# prozeda_0_2.net
KiCad netlist of a schematic drawn in EAGLE
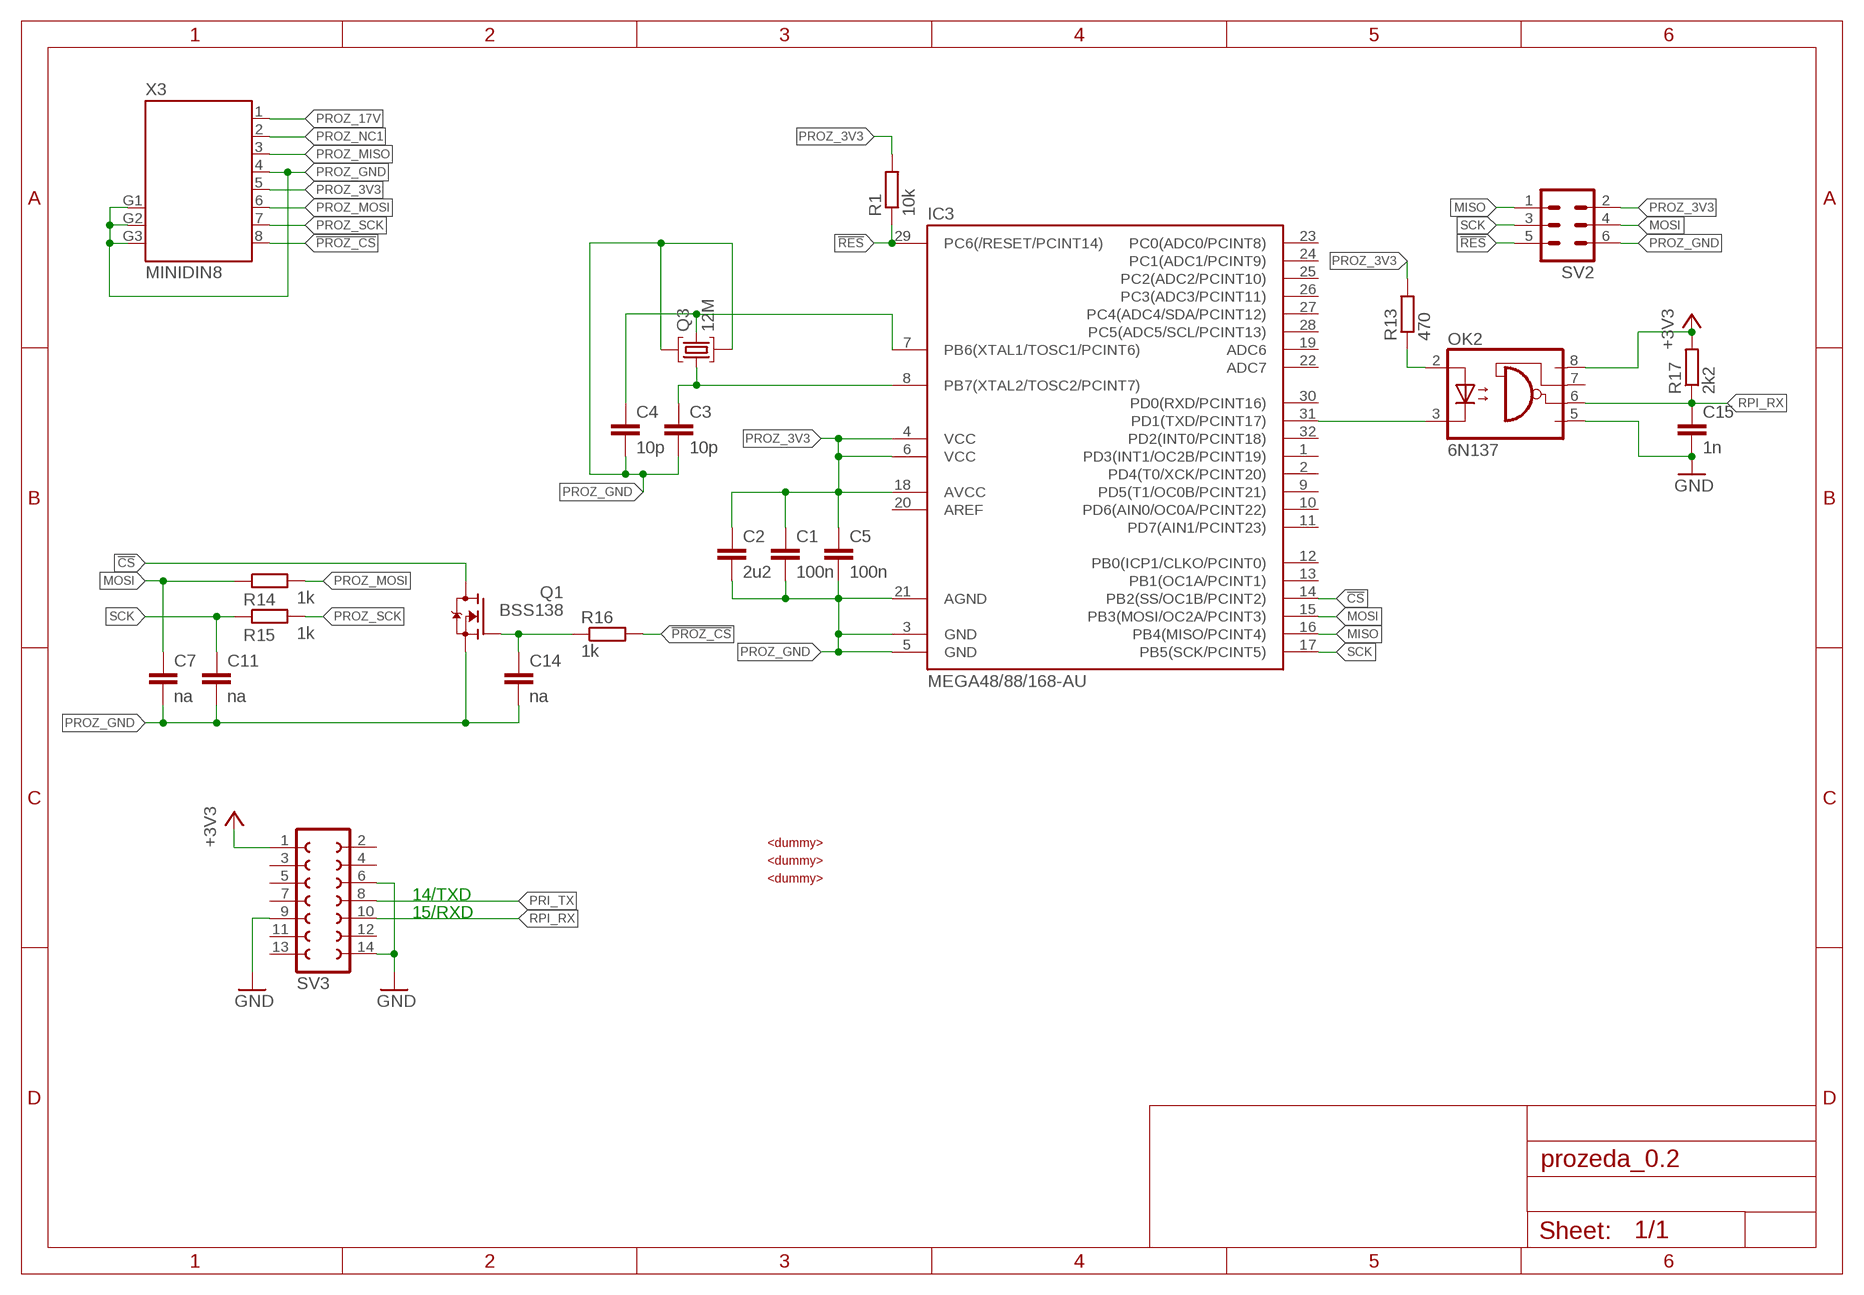
[diagram p0: schematic, sheet 1]

(export (version "E")
  (design (tool "Eeschema 10.0.6"))
  (components
    (comp (ref "C1")
      (value "100n")
      (footprint "eagle-import:C0603")
      (libsource (lib "eagle-import") (part "C-EUC0603"))
    )
    (comp (ref "C2")
      (value "2u2")
      (footprint "eagle-import:C0805")
      (libsource (lib "eagle-import") (part "C-EUC0805"))
    )
    (comp (ref "C3")
      (value "10p")
      (footprint "eagle-import:C0603")
      (libsource (lib "eagle-import") (part "C-EUC0603"))
    )
    (comp (ref "C4")
      (value "10p")
      (footprint "eagle-import:C0603")
      (libsource (lib "eagle-import") (part "C-EUC0603"))
    )
    (comp (ref "C5")
      (value "100n")
      (footprint "eagle-import:C0603")
      (libsource (lib "eagle-import") (part "C-EUC0603"))
    )
    (comp (ref "C7")
      (value "na")
      (footprint "eagle-import:C0603")
      (libsource (lib "eagle-import") (part "C-EUC0603"))
    )
    (comp (ref "C11")
      (value "na")
      (footprint "eagle-import:C0603")
      (libsource (lib "eagle-import") (part "C-EUC0603"))
    )
    (comp (ref "C14")
      (value "na")
      (footprint "eagle-import:C0603")
      (libsource (lib "eagle-import") (part "C-EUC0603"))
    )
    (comp (ref "C15")
      (value "1n")
      (footprint "eagle-import:C0603")
      (libsource (lib "eagle-import") (part "C-EUC0603"))
    )
    (comp (ref "IC3")
      (value "MEGA48/88/168-AU")
      (footprint "eagle-import:TQFP32-08")
      (libsource (lib "eagle-import") (part "MEGA48/88/168-AU"))
    )
    (comp (ref "OK2")
      (value "6N137")
      (footprint "eagle-import:DIL08")
      (libsource (lib "eagle-import") (part "6N137"))
    )
    (comp (ref "Q1")
      (value "BSS138")
      (footprint "eagle-import:SOT23")
      (libsource (lib "eagle-import") (part "BSS138"))
    )
    (comp (ref "Q3")
      (value "12M")
      (footprint "eagle-import:MJ")
      (libsource (lib "eagle-import") (part "SMD4PADMJ"))
    )
    (comp (ref "R1")
      (value "10k")
      (footprint "eagle-import:R0603")
      (libsource (lib "eagle-import") (part "R-EU_R0603"))
    )
    (comp (ref "R13")
      (value "470")
      (footprint "eagle-import:R0603")
      (libsource (lib "eagle-import") (part "R-EU_R0603"))
    )
    (comp (ref "R14")
      (value "1k")
      (footprint "eagle-import:R0603")
      (libsource (lib "eagle-import") (part "R-EU_R0603"))
    )
    (comp (ref "R15")
      (value "1k")
      (footprint "eagle-import:R0603")
      (libsource (lib "eagle-import") (part "R-EU_R0603"))
    )
    (comp (ref "R16")
      (value "1k")
      (footprint "eagle-import:R0603")
      (libsource (lib "eagle-import") (part "R-EU_R0603"))
    )
    (comp (ref "R17")
      (value "2k2")
      (footprint "eagle-import:R0603")
      (libsource (lib "eagle-import") (part "R-EU_R0603"))
    )
    (comp (ref "SV2")
      (value "MA03-2")
      (footprint "eagle-import:MA03-2")
      (libsource (lib "eagle-import") (part "MA03-2"))
    )
    (comp (ref "SV3")
      (value "FE07-2")
      (footprint "eagle-import:FE07-2")
      (libsource (lib "eagle-import") (part "FE07-2"))
    )
    (comp (ref "U$1")
      (value "DUMMY")
      (footprint "eagle-import:DUMMY")
      (libsource (lib "eagle-import") (part "DUMMY"))
    )
    (comp (ref "U$2")
      (value "DUMMY")
      (footprint "eagle-import:DUMMY")
      (libsource (lib "eagle-import") (part "DUMMY"))
    )
    (comp (ref "U$3")
      (value "DUMMY")
      (footprint "eagle-import:DUMMY")
      (libsource (lib "eagle-import") (part "DUMMY"))
    )
    (comp (ref "X3")
      (value "MINIDIN8")
      (footprint "eagle-import:MINI-DIN8")
      (libsource (lib "eagle-import") (part "MINIDIN8"))
    )
  )
  (nets
    (net (code "1") (name "+3V3") (class "Default")
      (node (ref "OK2") (pin "8") (pinfunction "VCC_8") (pintype "passive"))
      (node (ref "R17") (pin "2") (pinfunction "2_2") (pintype "passive"))
      (node (ref "SV3") (pin "1") (pinfunction "1_1") (pintype "passive"))
    )
    (net (code "2") (name "/~{CS}") (class "Default")
      (node (ref "IC3") (pin "14") (pinfunction "PB2(SS/OC1B/PCINT2)_14") (pintype "bidirectional"))
      (node (ref "Q1") (pin "3") (pinfunction "D_3") (pintype "passive"))
    )
    (net (code "3") (name "/~{PROZ_CS}") (class "Default")
      (node (ref "R16") (pin "2") (pinfunction "2_2") (pintype "passive"))
      (node (ref "X3") (pin "8") (pinfunction "P$8_8") (pintype "bidirectional"))
    )
    (net (code "4") (name "/~{RES}") (class "Default")
      (node (ref "IC3") (pin "29") (pinfunction "PC6(/RESET/PCINT14)_29") (pintype "bidirectional"))
      (node (ref "R1") (pin "1") (pinfunction "1_1") (pintype "passive"))
      (node (ref "SV2") (pin "5") (pinfunction "5_5") (pintype "passive"))
    )
    (net (code "5") (name "GND") (class "Default")
      (node (ref "C15") (pin "2") (pinfunction "2_2") (pintype "passive"))
      (node (ref "OK2") (pin "5") (pinfunction "GND_5") (pintype "passive"))
      (node (ref "SV3") (pin "14") (pinfunction "14_14") (pintype "passive"))
      (node (ref "SV3") (pin "6") (pinfunction "6_6") (pintype "passive"))
      (node (ref "SV3") (pin "9") (pinfunction "9_9") (pintype "passive"))
    )
    (net (code "6") (name "MISO") (class "Default")
      (node (ref "IC3") (pin "16") (pinfunction "PB4(MISO/PCINT4)_16") (pintype "bidirectional"))
      (node (ref "SV2") (pin "1") (pinfunction "1_1") (pintype "passive"))
    )
    (net (code "7") (name "MOSI") (class "Default")
      (node (ref "C7") (pin "1") (pinfunction "1_1") (pintype "passive"))
      (node (ref "IC3") (pin "15") (pinfunction "PB3(MOSI/OC2A/PCINT3)_15") (pintype "bidirectional"))
      (node (ref "R14") (pin "1") (pinfunction "1_1") (pintype "passive"))
      (node (ref "SV2") (pin "4") (pinfunction "4_4") (pintype "passive"))
    )
    (net (code "8") (name "Net-(IC3-PB6(XTAL1{slash}TOSC1{slash}PCINT6))") (class "Default")
      (node (ref "C4") (pin "1") (pinfunction "1_1") (pintype "passive"))
      (node (ref "IC3") (pin "7") (pinfunction "PB6(XTAL1/TOSC1/PCINT6)_7") (pintype "bidirectional"))
      (node (ref "Q3") (pin "3") (pinfunction "3_3") (pintype "passive"))
    )
    (net (code "9") (name "Net-(IC3-PB7(XTAL2{slash}TOSC2{slash}PCINT7))") (class "Default")
      (node (ref "C3") (pin "1") (pinfunction "1_1") (pintype "passive"))
      (node (ref "IC3") (pin "8") (pinfunction "PB7(XTAL2/TOSC2/PCINT7)_8") (pintype "bidirectional"))
      (node (ref "Q3") (pin "1") (pinfunction "1_1") (pintype "passive"))
    )
    (net (code "10") (name "Net-(IC3-PD1(TXD{slash}PCINT17))") (class "Default")
      (node (ref "IC3") (pin "31") (pinfunction "PD1(TXD/PCINT17)_31") (pintype "bidirectional"))
      (node (ref "OK2") (pin "3") (pinfunction "C_3") (pintype "passive"))
    )
    (net (code "11") (name "Net-(OK2-A)") (class "Default")
      (node (ref "OK2") (pin "2") (pinfunction "A_2") (pintype "passive"))
      (node (ref "R13") (pin "1") (pinfunction "1_1") (pintype "passive"))
    )
    (net (code "12") (name "Net-(Q1-G)") (class "Default")
      (node (ref "C14") (pin "1") (pinfunction "1_1") (pintype "passive"))
      (node (ref "Q1") (pin "1") (pinfunction "G_1") (pintype "passive"))
      (node (ref "R16") (pin "1") (pinfunction "1_1") (pintype "passive"))
    )
    (net (code "13") (name "PRI_TX") (class "Default")
      (node (ref "SV3") (pin "8") (pinfunction "8_8") (pintype "passive"))
    )
    (net (code "14") (name "PROZ_3V3") (class "Default")
      (node (ref "C1") (pin "1") (pinfunction "1_1") (pintype "passive"))
      (node (ref "C2") (pin "1") (pinfunction "1_1") (pintype "passive"))
      (node (ref "C5") (pin "1") (pinfunction "1_1") (pintype "passive"))
      (node (ref "IC3") (pin "18") (pinfunction "AVCC_18") (pintype "passive"))
      (node (ref "IC3") (pin "4") (pinfunction "VCC_4") (pintype "power_in"))
      (node (ref "IC3") (pin "6") (pinfunction "VCC_6") (pintype "power_in"))
      (node (ref "R1") (pin "2") (pinfunction "2_2") (pintype "passive"))
      (node (ref "R13") (pin "2") (pinfunction "2_2") (pintype "passive"))
      (node (ref "SV2") (pin "2") (pinfunction "2_2") (pintype "passive"))
      (node (ref "X3") (pin "5") (pinfunction "P$5_5") (pintype "bidirectional"))
    )
    (net (code "15") (name "PROZ_17V") (class "Default")
      (node (ref "X3") (pin "1") (pinfunction "P$1_1") (pintype "bidirectional"))
    )
    (net (code "16") (name "PROZ_GND") (class "Default")
      (node (ref "C1") (pin "2") (pinfunction "2_2") (pintype "passive"))
      (node (ref "C11") (pin "2") (pinfunction "2_2") (pintype "passive"))
      (node (ref "C14") (pin "2") (pinfunction "2_2") (pintype "passive"))
      (node (ref "C2") (pin "2") (pinfunction "2_2") (pintype "passive"))
      (node (ref "C3") (pin "2") (pinfunction "2_2") (pintype "passive"))
      (node (ref "C4") (pin "2") (pinfunction "2_2") (pintype "passive"))
      (node (ref "C5") (pin "2") (pinfunction "2_2") (pintype "passive"))
      (node (ref "C7") (pin "2") (pinfunction "2_2") (pintype "passive"))
      (node (ref "IC3") (pin "21") (pinfunction "AGND_21") (pintype "power_in"))
      (node (ref "IC3") (pin "3") (pinfunction "GND_3") (pintype "power_in"))
      (node (ref "IC3") (pin "5") (pinfunction "GND_5") (pintype "power_in"))
      (node (ref "Q1") (pin "2") (pinfunction "S_2") (pintype "passive"))
      (node (ref "Q3") (pin "2") (pinfunction "2_2") (pintype "passive"))
      (node (ref "Q3") (pin "4") (pinfunction "4_4") (pintype "passive"))
      (node (ref "SV2") (pin "6") (pinfunction "6_6") (pintype "passive"))
      (node (ref "X3") (pin "4") (pinfunction "P$4_4") (pintype "bidirectional"))
      (node (ref "X3") (pin "G1") (pinfunction "P$9_G1") (pintype "bidirectional"))
      (node (ref "X3") (pin "G2") (pinfunction "P$10_G2") (pintype "bidirectional"))
      (node (ref "X3") (pin "G3") (pinfunction "P$11_G3") (pintype "bidirectional"))
    )
    (net (code "17") (name "PROZ_MISO") (class "Default")
      (node (ref "X3") (pin "3") (pinfunction "P$3_3") (pintype "bidirectional"))
    )
    (net (code "18") (name "PROZ_MOSI") (class "Default")
      (node (ref "R14") (pin "2") (pinfunction "2_2") (pintype "passive"))
      (node (ref "X3") (pin "6") (pinfunction "P$6_6") (pintype "bidirectional"))
    )
    (net (code "19") (name "PROZ_NC1") (class "Default")
      (node (ref "X3") (pin "2") (pinfunction "P$2_2") (pintype "bidirectional"))
    )
    (net (code "20") (name "PROZ_SCK") (class "Default")
      (node (ref "R15") (pin "2") (pinfunction "2_2") (pintype "passive"))
      (node (ref "X3") (pin "7") (pinfunction "P$7_7") (pintype "bidirectional"))
    )
    (net (code "21") (name "RPI_RX") (class "Default")
      (node (ref "C15") (pin "1") (pinfunction "1_1") (pintype "passive"))
      (node (ref "OK2") (pin "6") (pinfunction "VO_6") (pintype "passive"))
      (node (ref "R17") (pin "1") (pinfunction "1_1") (pintype "passive"))
      (node (ref "SV3") (pin "10") (pinfunction "10_10") (pintype "passive"))
    )
    (net (code "22") (name "SCK") (class "Default")
      (node (ref "C11") (pin "1") (pinfunction "1_1") (pintype "passive"))
      (node (ref "IC3") (pin "17") (pinfunction "PB5(SCK/PCINT5)_17") (pintype "bidirectional"))
      (node (ref "R15") (pin "1") (pinfunction "1_1") (pintype "passive"))
      (node (ref "SV2") (pin "3") (pinfunction "3_3") (pintype "passive"))
    )
    (net (code "23") (name "unconnected-(IC3-ADC6-Pad19)") (class "Default")
      (node (ref "IC3") (pin "19") (pinfunction "ADC6_19") (pintype "passive"))
    )
    (net (code "24") (name "unconnected-(IC3-ADC7-Pad22)") (class "Default")
      (node (ref "IC3") (pin "22") (pinfunction "ADC7_22") (pintype "passive"))
    )
    (net (code "25") (name "unconnected-(IC3-AREF-Pad20)") (class "Default")
      (node (ref "IC3") (pin "20") (pinfunction "AREF_20") (pintype "passive"))
    )
    (net (code "26") (name "unconnected-(IC3-PB0(ICP1{slash}CLKO{slash}PCINT0)-Pad12)") (class "Default")
      (node (ref "IC3") (pin "12") (pinfunction "PB0(ICP1/CLKO/PCINT0)_12") (pintype "bidirectional"))
    )
    (net (code "27") (name "unconnected-(IC3-PB1(OC1A{slash}PCINT1)-Pad13)") (class "Default")
      (node (ref "IC3") (pin "13") (pinfunction "PB1(OC1A/PCINT1)_13") (pintype "bidirectional"))
    )
    (net (code "28") (name "unconnected-(IC3-PC0(ADC0{slash}PCINT8)-Pad23)") (class "Default")
      (node (ref "IC3") (pin "23") (pinfunction "PC0(ADC0/PCINT8)_23") (pintype "bidirectional"))
    )
    (net (code "29") (name "unconnected-(IC3-PC1(ADC1{slash}PCINT9)-Pad24)") (class "Default")
      (node (ref "IC3") (pin "24") (pinfunction "PC1(ADC1/PCINT9)_24") (pintype "bidirectional"))
    )
    (net (code "30") (name "unconnected-(IC3-PC2(ADC2{slash}PCINT10)-Pad25)") (class "Default")
      (node (ref "IC3") (pin "25") (pinfunction "PC2(ADC2/PCINT10)_25") (pintype "bidirectional"))
    )
    (net (code "31") (name "unconnected-(IC3-PC3(ADC3{slash}PCINT11)-Pad26)") (class "Default")
      (node (ref "IC3") (pin "26") (pinfunction "PC3(ADC3/PCINT11)_26") (pintype "bidirectional"))
    )
    (net (code "32") (name "unconnected-(IC3-PC4(ADC4{slash}SDA{slash}PCINT12)-Pad27)") (class "Default")
      (node (ref "IC3") (pin "27") (pinfunction "PC4(ADC4/SDA/PCINT12)_27") (pintype "bidirectional"))
    )
    (net (code "33") (name "unconnected-(IC3-PC5(ADC5{slash}SCL{slash}PCINT13)-Pad28)") (class "Default")
      (node (ref "IC3") (pin "28") (pinfunction "PC5(ADC5/SCL/PCINT13)_28") (pintype "bidirectional"))
    )
    (net (code "34") (name "unconnected-(IC3-PD0(RXD{slash}PCINT16)-Pad30)") (class "Default")
      (node (ref "IC3") (pin "30") (pinfunction "PD0(RXD/PCINT16)_30") (pintype "bidirectional"))
    )
    (net (code "35") (name "unconnected-(IC3-PD2(INT0{slash}PCINT18)-Pad32)") (class "Default")
      (node (ref "IC3") (pin "32") (pinfunction "PD2(INT0/PCINT18)_32") (pintype "bidirectional"))
    )
    (net (code "36") (name "unconnected-(IC3-PD3(INT1{slash}OC2B{slash}PCINT19)-Pad1)") (class "Default")
      (node (ref "IC3") (pin "1") (pinfunction "PD3(INT1/OC2B/PCINT19)_1") (pintype "bidirectional"))
    )
    (net (code "37") (name "unconnected-(IC3-PD4(T0{slash}XCK{slash}PCINT20)-Pad2)") (class "Default")
      (node (ref "IC3") (pin "2") (pinfunction "PD4(T0/XCK/PCINT20)_2") (pintype "bidirectional"))
    )
    (net (code "38") (name "unconnected-(IC3-PD5(T1{slash}OC0B{slash}PCINT21)-Pad9)") (class "Default")
      (node (ref "IC3") (pin "9") (pinfunction "PD5(T1/OC0B/PCINT21)_9") (pintype "bidirectional"))
    )
    (net (code "39") (name "unconnected-(IC3-PD6(AIN0{slash}OC0A{slash}PCINT22)-Pad10)") (class "Default")
      (node (ref "IC3") (pin "10") (pinfunction "PD6(AIN0/OC0A/PCINT22)_10") (pintype "bidirectional"))
    )
    (net (code "40") (name "unconnected-(IC3-PD7(AIN1{slash}PCINT23)-Pad11)") (class "Default")
      (node (ref "IC3") (pin "11") (pinfunction "PD7(AIN1/PCINT23)_11") (pintype "bidirectional"))
    )
    (net (code "41") (name "unconnected-(OK2-VE-Pad7)") (class "Default")
      (node (ref "OK2") (pin "7") (pinfunction "VE_7") (pintype "passive"))
    )
    (net (code "42") (name "unconnected-(SV3-Pad2)") (class "Default")
      (node (ref "SV3") (pin "2") (pinfunction "2_2") (pintype "passive"))
    )
    (net (code "43") (name "unconnected-(SV3-Pad3)") (class "Default")
      (node (ref "SV3") (pin "3") (pinfunction "3_3") (pintype "passive"))
    )
    (net (code "44") (name "unconnected-(SV3-Pad4)") (class "Default")
      (node (ref "SV3") (pin "4") (pinfunction "4_4") (pintype "passive"))
    )
    (net (code "45") (name "unconnected-(SV3-Pad5)") (class "Default")
      (node (ref "SV3") (pin "5") (pinfunction "5_5") (pintype "passive"))
    )
    (net (code "46") (name "unconnected-(SV3-Pad7)") (class "Default")
      (node (ref "SV3") (pin "7") (pinfunction "7_7") (pintype "passive"))
    )
    (net (code "47") (name "unconnected-(SV3-Pad11)") (class "Default")
      (node (ref "SV3") (pin "11") (pinfunction "11_11") (pintype "passive"))
    )
    (net (code "48") (name "unconnected-(SV3-Pad12)") (class "Default")
      (node (ref "SV3") (pin "12") (pinfunction "12_12") (pintype "passive"))
    )
    (net (code "49") (name "unconnected-(SV3-Pad13)") (class "Default")
      (node (ref "SV3") (pin "13") (pinfunction "13_13") (pintype "passive"))
    )
  )
)
